# SCH_DekiSuki_2026-05-25.net
KiCad netlist of a schematic drawn in EasyEDA
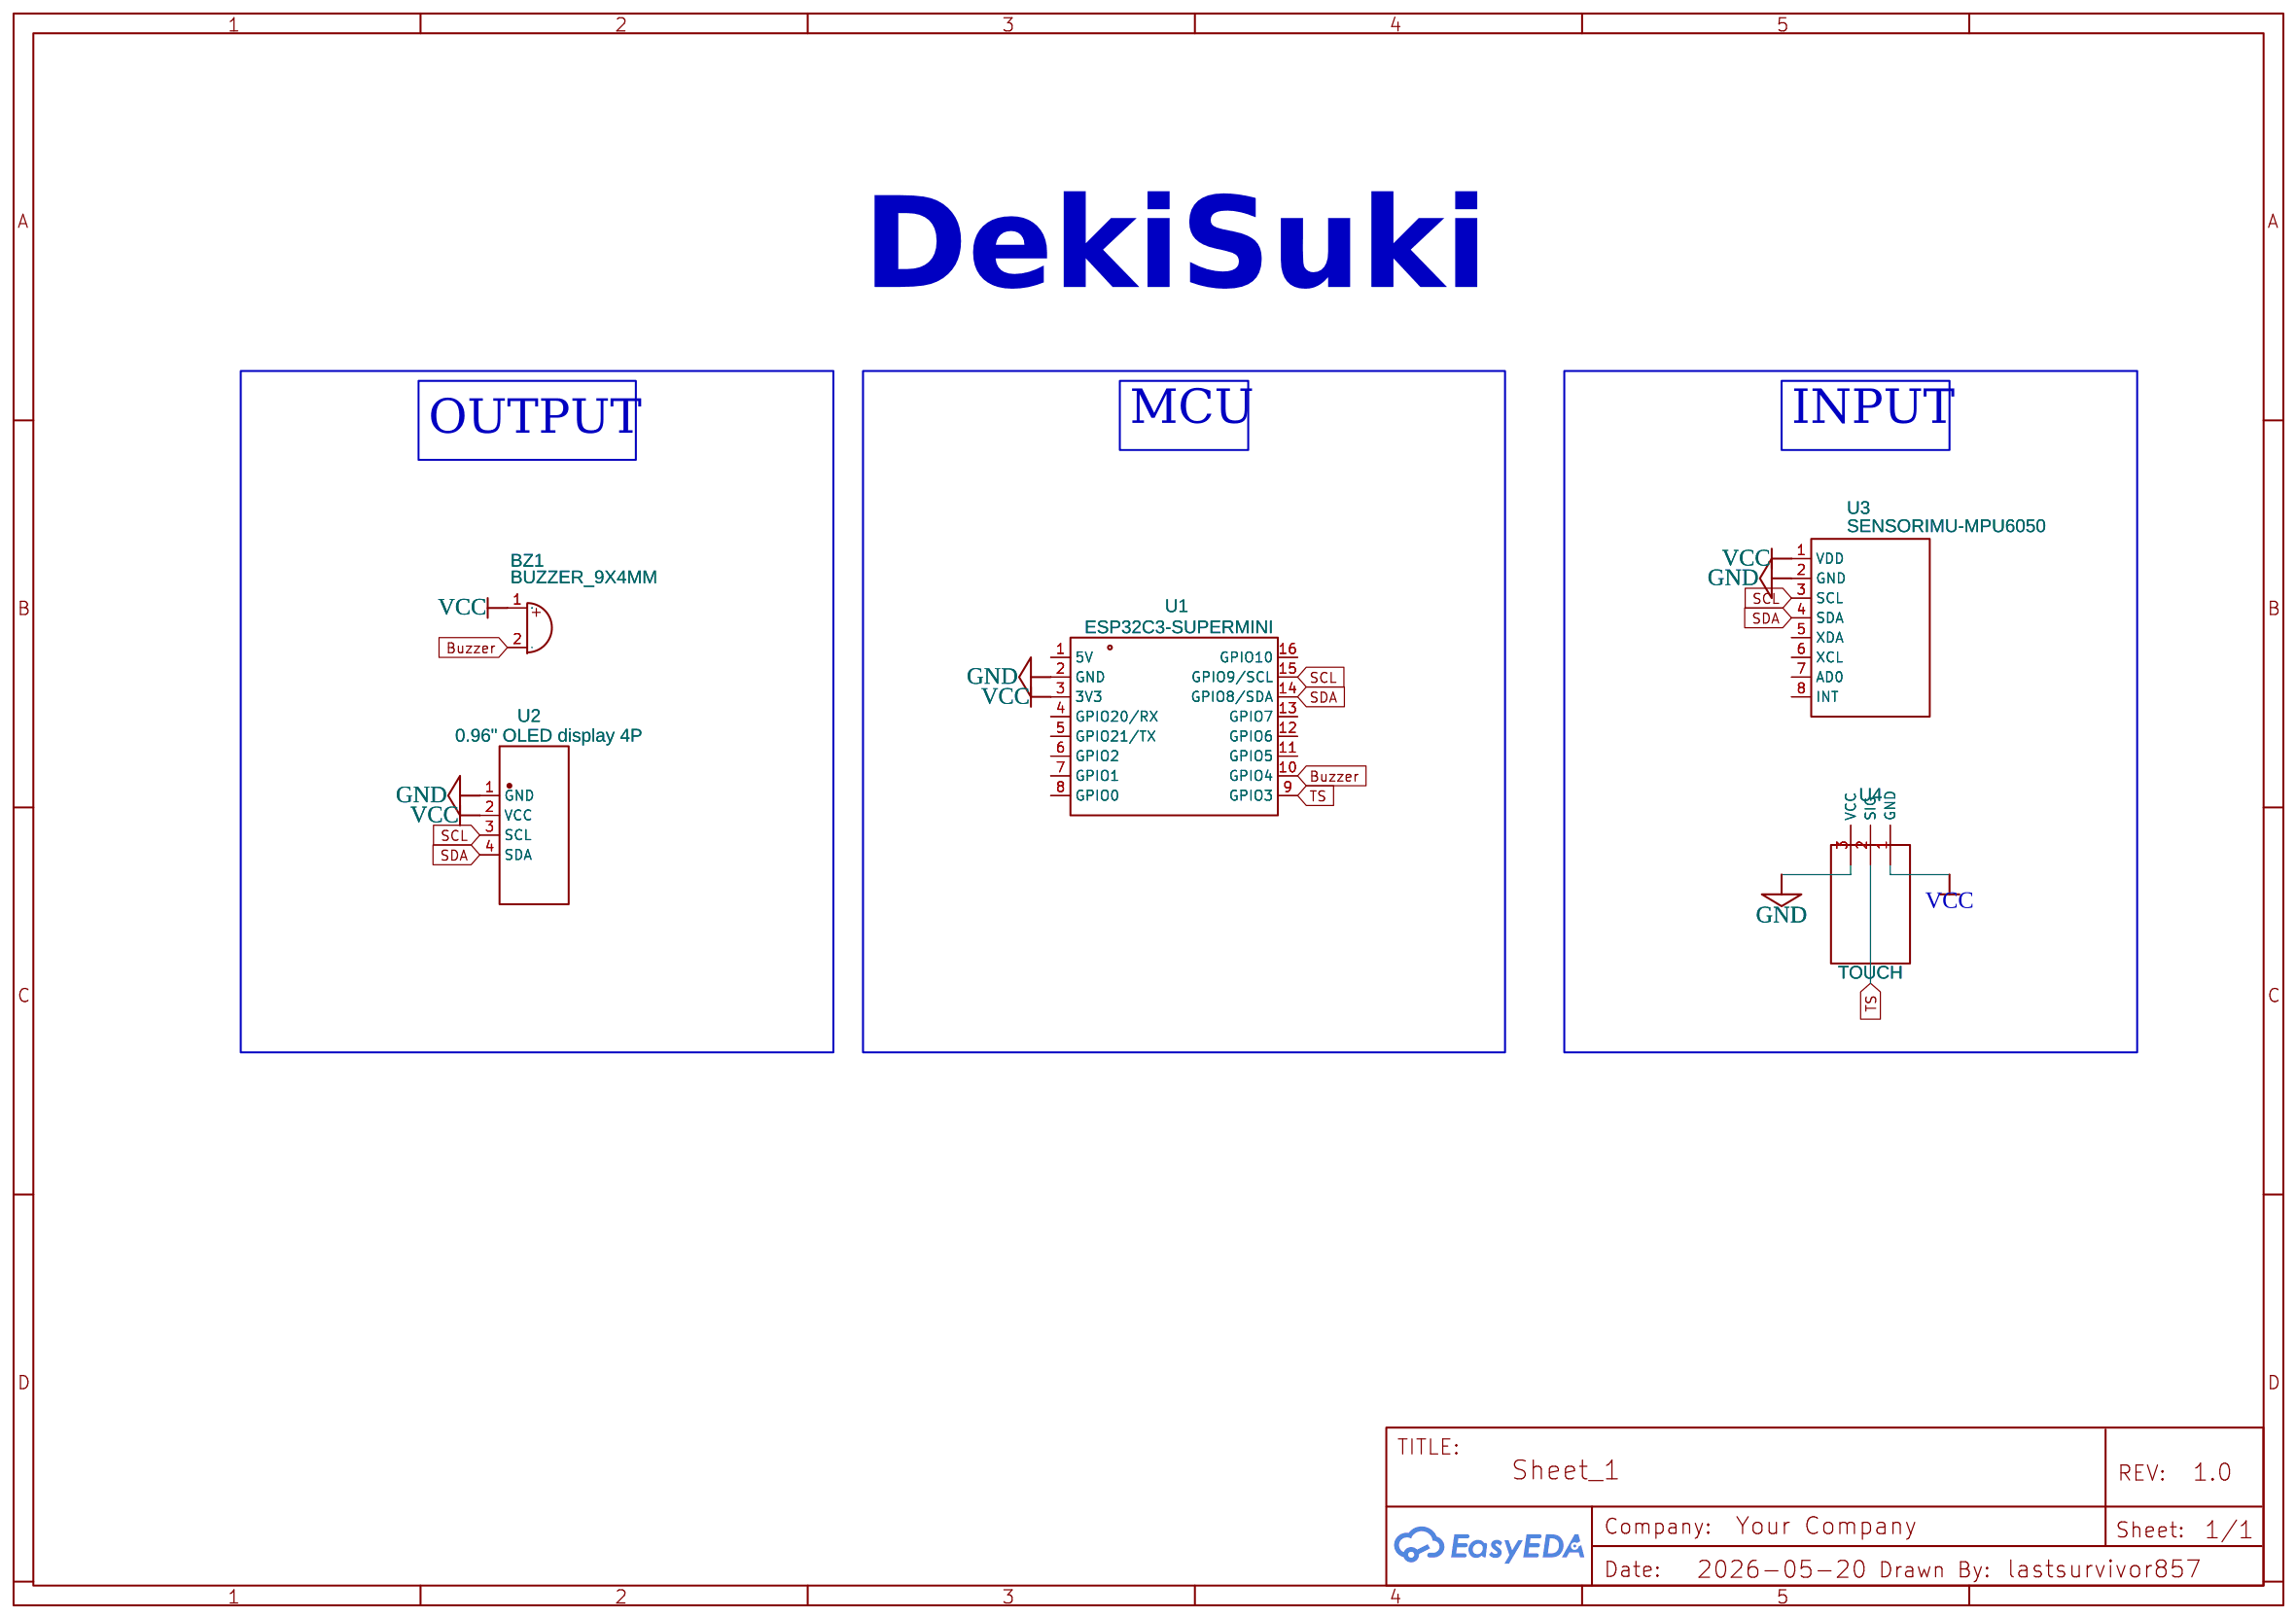
[diagram p0: schematic sheet]

(export (version "E")
  (design (tool "Eeschema 10.0.6"))
  (components
    (comp (ref "BZ1") (value "BUZZER_9X4MM") (libsource (lib "") (part "Device_Buzzer")))
    (comp (ref "U1")
      (value "ESP32C3-SUPERMINI")
      (fields (field (name "Manufacturer Part") "ESP32C3-SuperMini"))
      (libsource (lib "") (part "ESP32C3-SUPERMINI COPY"))
    )
    (comp (ref "U2")
      (value "0.96\" OLED display 4P")
      (fields
        (field (name "Manufacturer Part") "ZJY096S0700BG01蓝色")
        (field (name "Manufacturer") "郑州中景园电子技术有限公司")
      )
      (libsource (lib "") (part "0.96{dblquote} OLED display 4P"))
    )
    (comp (ref "U3") (value "SENSORIMU-MPU6050") (libsource (lib "") (part "SENSORIMU-MPU6050")))
    (comp (ref "U4") (value "TOUCH") (libsource (lib "") (part "CAPACITIVE TOUCH GND-SIG-VCC COPY")))
  )
  (nets
    (net (code "1") (name "Buzzer") (class "Default")
      (node (ref "BZ1") (pin "2") (pinfunction "-_2") (pintype "unspecified"))
      (node (ref "U1") (pin "10") (pinfunction "GPIO4_10") (pintype "unspecified"))
    )
    (net (code "2") (name "GND") (class "Default")
      (node (ref "U1") (pin "2") (pinfunction "GND_2") (pintype "unspecified"))
      (node (ref "U2") (pin "1") (pinfunction "GND_1") (pintype "unspecified"))
      (node (ref "U3") (pin "2") (pinfunction "GND_2") (pintype "unspecified"))
      (node (ref "U4") (pin "3") (pinfunction "VCC_3") (pintype "unspecified"))
    )
    (net (code "3") (name "SCL") (class "Default")
      (node (ref "U1") (pin "15") (pinfunction "GPIO9/SCL_15") (pintype "unspecified"))
      (node (ref "U2") (pin "3") (pinfunction "SCL_3") (pintype "unspecified"))
      (node (ref "U3") (pin "3") (pinfunction "SCL_3") (pintype "unspecified"))
    )
    (net (code "4") (name "SDA") (class "Default")
      (node (ref "U1") (pin "14") (pinfunction "GPIO8/SDA_14") (pintype "unspecified"))
      (node (ref "U2") (pin "4") (pinfunction "SDA_4") (pintype "unspecified"))
      (node (ref "U3") (pin "4") (pinfunction "SDA_4") (pintype "unspecified"))
    )
    (net (code "5") (name "TS") (class "Default")
      (node (ref "U1") (pin "9") (pinfunction "GPIO3_9") (pintype "unspecified"))
      (node (ref "U4") (pin "2") (pinfunction "SIG_2") (pintype "unspecified"))
    )
    (net (code "6") (name "VCC") (class "Default")
      (node (ref "BZ1") (pin "1") (pinfunction "+_1") (pintype "unspecified"))
      (node (ref "U1") (pin "3") (pinfunction "3V3_3") (pintype "unspecified"))
      (node (ref "U2") (pin "2") (pinfunction "VCC_2") (pintype "unspecified"))
      (node (ref "U3") (pin "1") (pinfunction "VDD_1") (pintype "unspecified"))
      (node (ref "U4") (pin "1") (pinfunction "GND_1") (pintype "unspecified"))
    )
    (net (code "7") (name "unconnected-(U1-5V-Pad1)") (class "Default")
      (node (ref "U1") (pin "1") (pinfunction "5V_1") (pintype "unspecified"))
    )
    (net (code "8") (name "unconnected-(U1-GPIO0-Pad8)") (class "Default")
      (node (ref "U1") (pin "8") (pinfunction "GPIO0_8") (pintype "unspecified"))
    )
    (net (code "9") (name "unconnected-(U1-GPIO1-Pad7)") (class "Default")
      (node (ref "U1") (pin "7") (pinfunction "GPIO1_7") (pintype "unspecified"))
    )
    (net (code "10") (name "unconnected-(U1-GPIO2-Pad6)") (class "Default")
      (node (ref "U1") (pin "6") (pinfunction "GPIO2_6") (pintype "unspecified"))
    )
    (net (code "11") (name "unconnected-(U1-GPIO5-Pad11)") (class "Default")
      (node (ref "U1") (pin "11") (pinfunction "GPIO5_11") (pintype "unspecified"))
    )
    (net (code "12") (name "unconnected-(U1-GPIO6-Pad12)") (class "Default")
      (node (ref "U1") (pin "12") (pinfunction "GPIO6_12") (pintype "unspecified"))
    )
    (net (code "13") (name "unconnected-(U1-GPIO7-Pad13)") (class "Default")
      (node (ref "U1") (pin "13") (pinfunction "GPIO7_13") (pintype "unspecified"))
    )
    (net (code "14") (name "unconnected-(U1-GPIO10-Pad16)") (class "Default")
      (node (ref "U1") (pin "16") (pinfunction "GPIO10_16") (pintype "unspecified"))
    )
    (net (code "15") (name "unconnected-(U1-GPIO20{slash}RX-Pad4)") (class "Default")
      (node (ref "U1") (pin "4") (pinfunction "GPIO20/RX_4") (pintype "unspecified"))
    )
    (net (code "16") (name "unconnected-(U1-GPIO21{slash}TX-Pad5)") (class "Default")
      (node (ref "U1") (pin "5") (pinfunction "GPIO21/TX_5") (pintype "unspecified"))
    )
    (net (code "17") (name "unconnected-(U3-AD0-Pad7)") (class "Default")
      (node (ref "U3") (pin "7") (pinfunction "AD0_7") (pintype "unspecified"))
    )
    (net (code "18") (name "unconnected-(U3-INT-Pad8)") (class "Default")
      (node (ref "U3") (pin "8") (pinfunction "INT_8") (pintype "unspecified"))
    )
    (net (code "19") (name "unconnected-(U3-XCL-Pad6)") (class "Default")
      (node (ref "U3") (pin "6") (pinfunction "XCL_6") (pintype "unspecified"))
    )
    (net (code "20") (name "unconnected-(U3-XDA-Pad5)") (class "Default")
      (node (ref "U3") (pin "5") (pinfunction "XDA_5") (pintype "unspecified"))
    )
  )
)
